# RFID-Parking-System.net
KiCad netlist of a schematic drawn in EAGLE
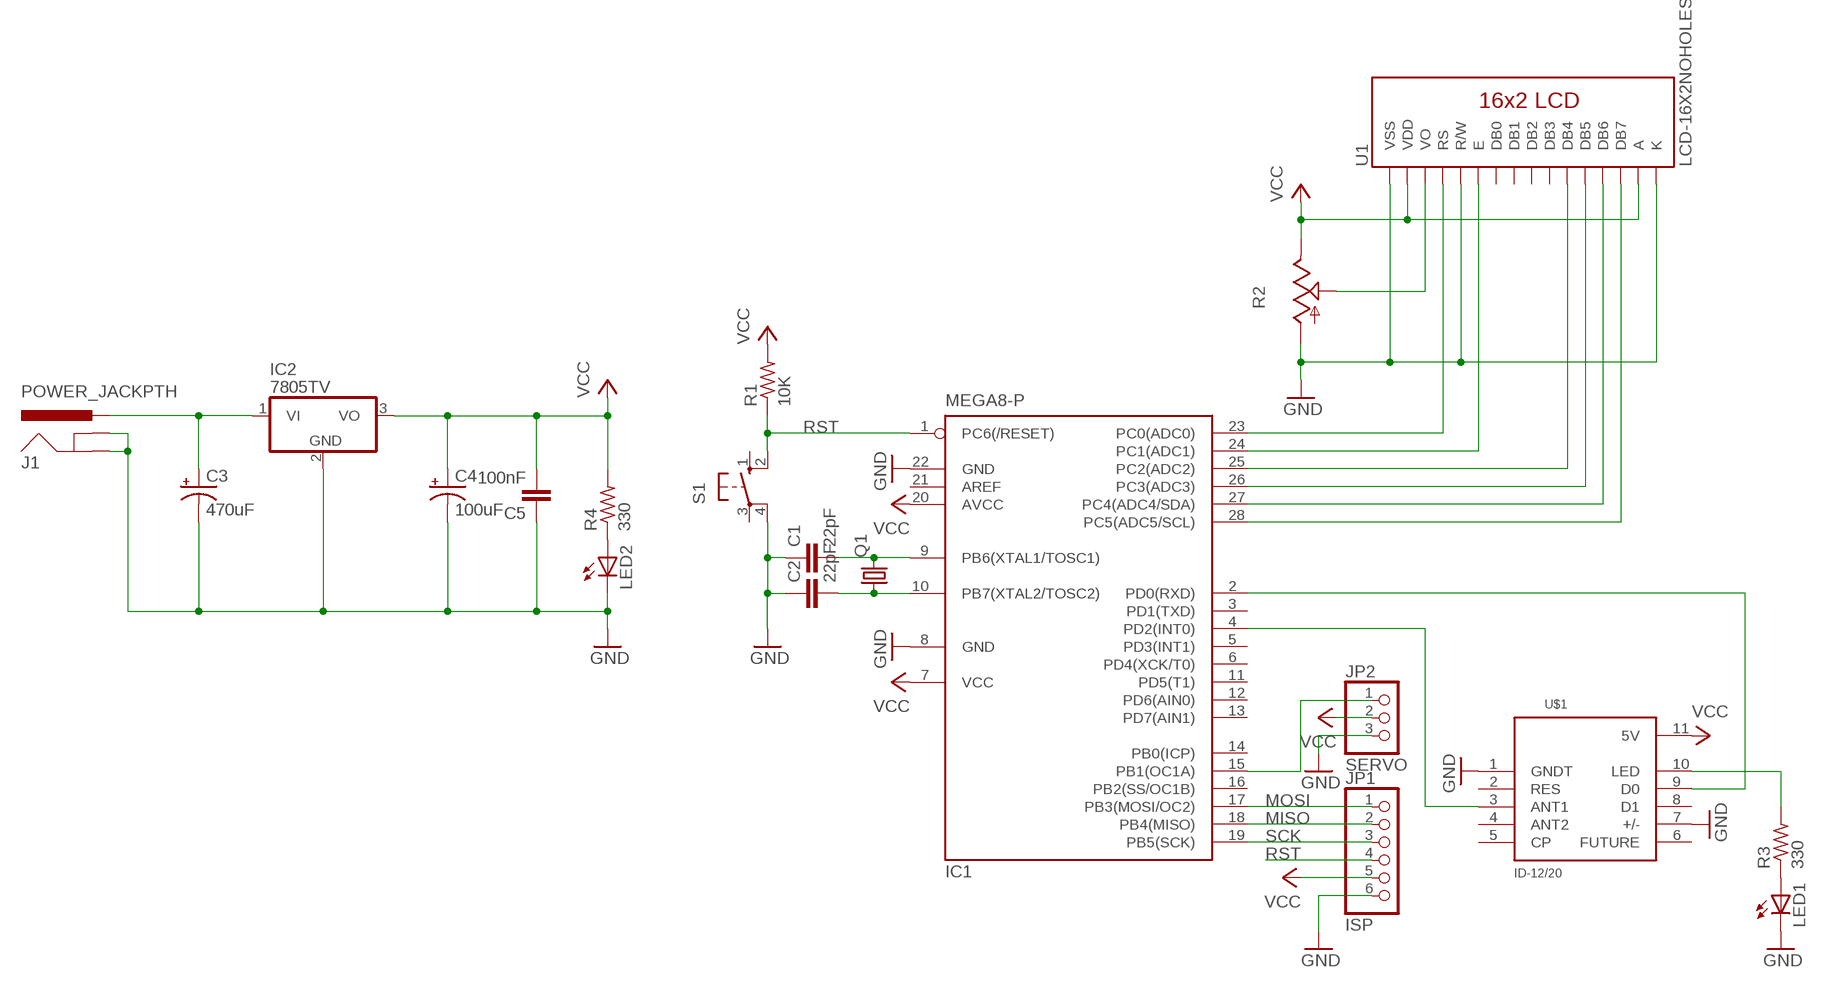
[diagram p0: schematic, sheet 1]

(export (version "E")
  (design (tool "Eeschema 10.0.6"))
  (components
    (comp (ref "C1")
      (value "22pF")
      (footprint "eagle-import:C025-024X044")
      (libsource (lib "eagle-import") (part "C-EU025-024X044"))
    )
    (comp (ref "C2")
      (value "22pF")
      (footprint "eagle-import:C025-024X044")
      (libsource (lib "eagle-import") (part "C-EU025-024X044"))
    )
    (comp (ref "C3")
      (value "470uF")
      (footprint "eagle-import:E2,5-6")
      (libsource (lib "eagle-import") (part "CPOL-USE2.5-6"))
    )
    (comp (ref "C4")
      (value "100uF")
      (footprint "eagle-import:E2,5-6")
      (libsource (lib "eagle-import") (part "CPOL-USE2.5-6"))
    )
    (comp (ref "C5")
      (value "100nF")
      (footprint "eagle-import:C025-024X044")
      (libsource (lib "eagle-import") (part "C-EU025-024X044"))
    )
    (comp (ref "IC1")
      (value "MEGA8-P")
      (footprint "eagle-import:DIL28-3")
      (libsource (lib "eagle-import") (part "MEGA8-P"))
    )
    (comp (ref "IC2")
      (value "7805TV")
      (footprint "eagle-import:TO220V")
      (libsource (lib "eagle-import") (part "78TV05"))
    )
    (comp (ref "J1")
      (value "POWER_JACKPTH")
      (footprint "eagle-import:POWER_JACK_PTH")
      (libsource (lib "eagle-import") (part "POWER_JACKPTH"))
    )
    (comp (ref "JP1")
      (value "ISP")
      (footprint "eagle-import:1X06")
      (libsource (lib "eagle-import") (part "PINHD-1X6"))
    )
    (comp (ref "JP2")
      (value "SERVO")
      (footprint "eagle-import:1X03")
      (libsource (lib "eagle-import") (part "PINHD-1X3"))
    )
    (comp (ref "LED1")
      (value "LED3MM")
      (footprint "eagle-import:LED3MM")
      (libsource (lib "eagle-import") (part "LED3MM"))
    )
    (comp (ref "LED2")
      (value "LED3MM")
      (footprint "eagle-import:LED3MM")
      (libsource (lib "eagle-import") (part "LED3MM"))
    )
    (comp (ref "Q1")
      (value "CRYSTALHC49S")
      (footprint "eagle-import:HC49_S")
      (libsource (lib "eagle-import") (part "CRYSTALHC49S"))
    )
    (comp (ref "R1")
      (value "10K")
      (footprint "eagle-import:0207_10")
      (libsource (lib "eagle-import") (part "R-US_0207/10"))
    )
    (comp (ref "R2")
      (value "TRIM_US-CA6V")
      (footprint "eagle-import:CA6V")
      (libsource (lib "eagle-import") (part "TRIM_US-CA6V"))
    )
    (comp (ref "R3")
      (value "330")
      (footprint "eagle-import:0207_10")
      (libsource (lib "eagle-import") (part "R-US_0207/10"))
    )
    (comp (ref "R4")
      (value "330")
      (footprint "eagle-import:0207_10")
      (libsource (lib "eagle-import") (part "R-US_0207/10"))
    )
    (comp (ref "S1")
      (value "10-XX")
      (footprint "eagle-import:B3F-10XX")
      (fields (field (name "MPN") "B3F-1000"))
      (libsource (lib "eagle-import") (part "10-XX"))
    )
    (comp (ref "U$1")
      (value "ID-12/20")
      (footprint "eagle-import:ID-12")
      (libsource (lib "eagle-import") (part "ID-12/20"))
    )
    (comp (ref "U1")
      (value "LCD-16X2NOHOLES")
      (footprint "eagle-import:LCD-16X2_NOHOLES")
      (libsource (lib "eagle-import") (part "LCD-16X2NOHOLES"))
    )
  )
  (nets
    (net (code "1") (name "/MISO") (class "Default")
      (node (ref "IC1") (pin "18") (pinfunction "PB4(MISO)_18") (pintype "bidirectional"))
      (node (ref "JP1") (pin "2") (pinfunction "2_2") (pintype "passive"))
    )
    (net (code "2") (name "/MOSI") (class "Default")
      (node (ref "IC1") (pin "17") (pinfunction "PB3(MOSI/OC2)_17") (pintype "bidirectional"))
      (node (ref "JP1") (pin "1") (pinfunction "1_1") (pintype "passive"))
    )
    (net (code "3") (name "/RST") (class "Default")
      (node (ref "IC1") (pin "1") (pinfunction "PC6(/RESET)_1") (pintype "bidirectional"))
      (node (ref "JP1") (pin "4") (pinfunction "4_4") (pintype "passive"))
      (node (ref "R1") (pin "1") (pinfunction "1_1") (pintype "passive"))
      (node (ref "S1") (pin "2") (pinfunction "S1_2") (pintype "passive"))
    )
    (net (code "4") (name "/SCK") (class "Default")
      (node (ref "IC1") (pin "19") (pinfunction "PB5(SCK)_19") (pintype "bidirectional"))
      (node (ref "JP1") (pin "3") (pinfunction "3_3") (pintype "passive"))
    )
    (net (code "5") (name "GND") (class "Default")
      (node (ref "C1") (pin "1") (pinfunction "1_1") (pintype "passive"))
      (node (ref "C2") (pin "1") (pinfunction "1_1") (pintype "passive"))
      (node (ref "C3") (pin "-") (pinfunction "-_-") (pintype "passive"))
      (node (ref "C4") (pin "-") (pinfunction "-_-") (pintype "passive"))
      (node (ref "C5") (pin "1") (pinfunction "1_1") (pintype "passive"))
      (node (ref "IC1") (pin "22") (pinfunction "GND_22") (pintype "power_in"))
      (node (ref "IC1") (pin "8") (pinfunction "GND_8") (pintype "power_in"))
      (node (ref "IC2") (pin "2") (pinfunction "GND_2") (pintype "passive"))
      (node (ref "J1") (pin "GND") (pinfunction "GND_GND") (pintype "bidirectional"))
      (node (ref "J1") (pin "GNDBREAK") (pinfunction "GNDBREAK_GNDBREAK") (pintype "bidirectional"))
      (node (ref "JP1") (pin "6") (pinfunction "6_6") (pintype "passive"))
      (node (ref "JP2") (pin "3") (pinfunction "3_3") (pintype "passive"))
      (node (ref "LED1") (pin "K") (pinfunction "C_K") (pintype "passive"))
      (node (ref "LED2") (pin "K") (pinfunction "C_K") (pintype "passive"))
      (node (ref "R2") (pin "A") (pinfunction "A_A") (pintype "passive"))
      (node (ref "S1") (pin "4") (pinfunction "P1_4") (pintype "passive"))
      (node (ref "U$1") (pin "1") (pinfunction "GNDT_1") (pintype "bidirectional"))
      (node (ref "U$1") (pin "7") (pinfunction "+/-_7") (pintype "bidirectional"))
      (node (ref "U1") (pin "1") (pinfunction "VSS_1") (pintype "power_in"))
      (node (ref "U1") (pin "16") (pinfunction "K_16") (pintype "power_in"))
      (node (ref "U1") (pin "5") (pinfunction "R/W_5") (pintype "input"))
    )
    (net (code "6") (name "Net-(IC1-PB1(OC1A))") (class "Default")
      (node (ref "IC1") (pin "15") (pinfunction "PB1(OC1A)_15") (pintype "bidirectional"))
      (node (ref "JP2") (pin "1") (pinfunction "1_1") (pintype "passive"))
    )
    (net (code "7") (name "Net-(IC1-PB6(XTAL1{slash}TOSC1))") (class "Default")
      (node (ref "C1") (pin "2") (pinfunction "2_2") (pintype "passive"))
      (node (ref "IC1") (pin "9") (pinfunction "PB6(XTAL1/TOSC1)_9") (pintype "bidirectional"))
      (node (ref "Q1") (pin "2") (pinfunction "2_2") (pintype "passive"))
    )
    (net (code "8") (name "Net-(IC1-PB7(XTAL2{slash}TOSC2))") (class "Default")
      (node (ref "C2") (pin "2") (pinfunction "2_2") (pintype "passive"))
      (node (ref "IC1") (pin "10") (pinfunction "PB7(XTAL2/TOSC2)_10") (pintype "bidirectional"))
      (node (ref "Q1") (pin "1") (pinfunction "1_1") (pintype "passive"))
    )
    (net (code "9") (name "Net-(IC1-PC0(ADC0))") (class "Default")
      (node (ref "IC1") (pin "23") (pinfunction "PC0(ADC0)_23") (pintype "bidirectional"))
      (node (ref "U1") (pin "4") (pinfunction "RS_4") (pintype "input"))
    )
    (net (code "10") (name "Net-(IC1-PC1(ADC1))") (class "Default")
      (node (ref "IC1") (pin "24") (pinfunction "PC1(ADC1)_24") (pintype "bidirectional"))
      (node (ref "U1") (pin "6") (pinfunction "E_6") (pintype "input"))
    )
    (net (code "11") (name "Net-(IC1-PC2(ADC2))") (class "Default")
      (node (ref "IC1") (pin "25") (pinfunction "PC2(ADC2)_25") (pintype "bidirectional"))
      (node (ref "U1") (pin "11") (pinfunction "DB4_11") (pintype "bidirectional"))
    )
    (net (code "12") (name "Net-(IC1-PC3(ADC3))") (class "Default")
      (node (ref "IC1") (pin "26") (pinfunction "PC3(ADC3)_26") (pintype "bidirectional"))
      (node (ref "U1") (pin "12") (pinfunction "DB5_12") (pintype "bidirectional"))
    )
    (net (code "13") (name "Net-(IC1-PC4(ADC4{slash}SDA))") (class "Default")
      (node (ref "IC1") (pin "27") (pinfunction "PC4(ADC4/SDA)_27") (pintype "bidirectional"))
      (node (ref "U1") (pin "13") (pinfunction "DB6_13") (pintype "bidirectional"))
    )
    (net (code "14") (name "Net-(IC1-PC5(ADC5{slash}SCL))") (class "Default")
      (node (ref "IC1") (pin "28") (pinfunction "PC5(ADC5/SCL)_28") (pintype "bidirectional"))
      (node (ref "U1") (pin "14") (pinfunction "DB7_14") (pintype "bidirectional"))
    )
    (net (code "15") (name "Net-(IC1-PD0(RXD))") (class "Default")
      (node (ref "IC1") (pin "2") (pinfunction "PD0(RXD)_2") (pintype "bidirectional"))
      (node (ref "U$1") (pin "9") (pinfunction "D0_9") (pintype "bidirectional"))
    )
    (net (code "16") (name "Net-(IC1-PD2(INT0))") (class "Default")
      (node (ref "IC1") (pin "4") (pinfunction "PD2(INT0)_4") (pintype "bidirectional"))
      (node (ref "U$1") (pin "3") (pinfunction "ANT1_3") (pintype "bidirectional"))
    )
    (net (code "17") (name "Net-(IC2-VI)") (class "Default")
      (node (ref "C3") (pin "+") (pinfunction "+_+") (pintype "passive"))
      (node (ref "IC2") (pin "1") (pinfunction "VI_1") (pintype "input"))
      (node (ref "J1") (pin "PWR") (pinfunction "PWR_PWR") (pintype "bidirectional"))
    )
    (net (code "18") (name "Net-(LED1-PadA)") (class "Default")
      (node (ref "LED1") (pin "A") (pinfunction "A_A") (pintype "passive"))
      (node (ref "R3") (pin "1") (pinfunction "1_1") (pintype "passive"))
    )
    (net (code "19") (name "Net-(LED2-PadA)") (class "Default")
      (node (ref "LED2") (pin "A") (pinfunction "A_A") (pintype "passive"))
      (node (ref "R4") (pin "1") (pinfunction "1_1") (pintype "passive"))
    )
    (net (code "20") (name "Net-(U$1-LED)") (class "Default")
      (node (ref "R3") (pin "2") (pinfunction "2_2") (pintype "passive"))
      (node (ref "U$1") (pin "10") (pinfunction "LED_10") (pintype "bidirectional"))
    )
    (net (code "21") (name "Net-(U1-VO)") (class "Default")
      (node (ref "R2") (pin "S") (pinfunction "S_S") (pintype "passive"))
      (node (ref "U1") (pin "3") (pinfunction "VO_3") (pintype "bidirectional"))
    )
    (net (code "22") (name "VCC") (class "Default")
      (node (ref "C4") (pin "+") (pinfunction "+_+") (pintype "passive"))
      (node (ref "C5") (pin "2") (pinfunction "2_2") (pintype "passive"))
      (node (ref "IC1") (pin "20") (pinfunction "AVCC_20") (pintype "power_in"))
      (node (ref "IC1") (pin "7") (pinfunction "VCC_7") (pintype "power_in"))
      (node (ref "IC2") (pin "3") (pinfunction "VO_3") (pintype "passive"))
      (node (ref "JP1") (pin "5") (pinfunction "5_5") (pintype "passive"))
      (node (ref "JP2") (pin "2") (pinfunction "2_2") (pintype "passive"))
      (node (ref "R1") (pin "2") (pinfunction "2_2") (pintype "passive"))
      (node (ref "R2") (pin "E") (pinfunction "E_E") (pintype "passive"))
      (node (ref "R4") (pin "2") (pinfunction "2_2") (pintype "passive"))
      (node (ref "U$1") (pin "11") (pinfunction "5V_11") (pintype "bidirectional"))
      (node (ref "U1") (pin "15") (pinfunction "A_15") (pintype "power_in"))
      (node (ref "U1") (pin "2") (pinfunction "VDD_2") (pintype "power_in"))
    )
    (net (code "23") (name "unconnected-(IC1-AREF-Pad21)") (class "Default")
      (node (ref "IC1") (pin "21") (pinfunction "AREF_21") (pintype "passive"))
    )
    (net (code "24") (name "unconnected-(IC1-PB0(ICP)-Pad14)") (class "Default")
      (node (ref "IC1") (pin "14") (pinfunction "PB0(ICP)_14") (pintype "bidirectional"))
    )
    (net (code "25") (name "unconnected-(IC1-PB2(SS{slash}OC1B)-Pad16)") (class "Default")
      (node (ref "IC1") (pin "16") (pinfunction "PB2(SS/OC1B)_16") (pintype "bidirectional"))
    )
    (net (code "26") (name "unconnected-(IC1-PD1(TXD)-Pad3)") (class "Default")
      (node (ref "IC1") (pin "3") (pinfunction "PD1(TXD)_3") (pintype "bidirectional"))
    )
    (net (code "27") (name "unconnected-(IC1-PD3(INT1)-Pad5)") (class "Default")
      (node (ref "IC1") (pin "5") (pinfunction "PD3(INT1)_5") (pintype "bidirectional"))
    )
    (net (code "28") (name "unconnected-(IC1-PD4(XCK{slash}T0)-Pad6)") (class "Default")
      (node (ref "IC1") (pin "6") (pinfunction "PD4(XCK/T0)_6") (pintype "bidirectional"))
    )
    (net (code "29") (name "unconnected-(IC1-PD5(T1)-Pad11)") (class "Default")
      (node (ref "IC1") (pin "11") (pinfunction "PD5(T1)_11") (pintype "bidirectional"))
    )
    (net (code "30") (name "unconnected-(IC1-PD6(AIN0)-Pad12)") (class "Default")
      (node (ref "IC1") (pin "12") (pinfunction "PD6(AIN0)_12") (pintype "bidirectional"))
    )
    (net (code "31") (name "unconnected-(IC1-PD7(AIN1)-Pad13)") (class "Default")
      (node (ref "IC1") (pin "13") (pinfunction "PD7(AIN1)_13") (pintype "bidirectional"))
    )
    (net (code "32") (name "unconnected-(S1-P-Pad3)") (class "Default")
      (node (ref "S1") (pin "3") (pinfunction "P_3") (pintype "passive"))
    )
    (net (code "33") (name "unconnected-(S1-S-Pad1)") (class "Default")
      (node (ref "S1") (pin "1") (pinfunction "S_1") (pintype "passive"))
    )
    (net (code "34") (name "unconnected-(U$1-ANT2-Pad4)") (class "Default")
      (node (ref "U$1") (pin "4") (pinfunction "ANT2_4") (pintype "bidirectional"))
    )
    (net (code "35") (name "unconnected-(U$1-CP-Pad5)") (class "Default")
      (node (ref "U$1") (pin "5") (pinfunction "CP_5") (pintype "bidirectional"))
    )
    (net (code "36") (name "unconnected-(U$1-D1-Pad8)") (class "Default")
      (node (ref "U$1") (pin "8") (pinfunction "D1_8") (pintype "bidirectional"))
    )
    (net (code "37") (name "unconnected-(U$1-FUTURE-Pad6)") (class "Default")
      (node (ref "U$1") (pin "6") (pinfunction "FUTURE_6") (pintype "bidirectional"))
    )
    (net (code "38") (name "unconnected-(U$1-RES-Pad2)") (class "Default")
      (node (ref "U$1") (pin "2") (pinfunction "RES_2") (pintype "bidirectional"))
    )
    (net (code "39") (name "unconnected-(U1-DB0-Pad7)") (class "Default")
      (node (ref "U1") (pin "7") (pinfunction "DB0_7") (pintype "bidirectional"))
    )
    (net (code "40") (name "unconnected-(U1-DB1-Pad8)") (class "Default")
      (node (ref "U1") (pin "8") (pinfunction "DB1_8") (pintype "bidirectional"))
    )
    (net (code "41") (name "unconnected-(U1-DB2-Pad9)") (class "Default")
      (node (ref "U1") (pin "9") (pinfunction "DB2_9") (pintype "bidirectional"))
    )
    (net (code "42") (name "unconnected-(U1-DB3-Pad10)") (class "Default")
      (node (ref "U1") (pin "10") (pinfunction "DB3_10") (pintype "bidirectional"))
    )
  )
)
